# 05I2S.net
KiCad netlist of a schematic drawn in Altium Designer
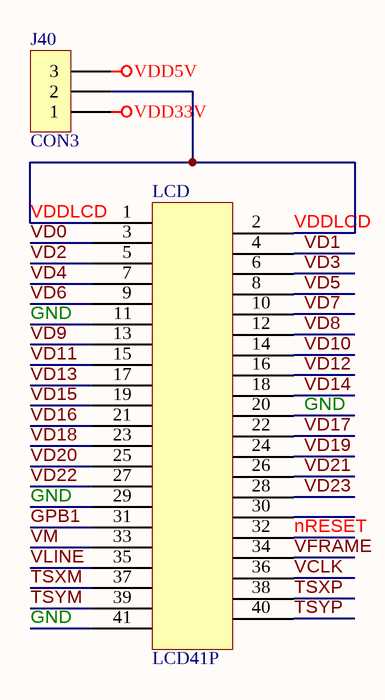
[diagram p0: 05I2S.SchDoc]

(export (version "E")
  (design (tool "Eeschema 10.0.6"))
  (components
    (comp (ref "J40")
      (value "CON3")
      (footprint "HDR1X3")
      (description "Connector")
      (libsource (lib "*") (part "CON3"))
    )
    (comp (ref "LCD") (value "LCD41P") (footprint "FPC40") (libsource (lib "*") (part "LCD41P")))
  )
  (nets
    (net (code "1") (name "/GND") (class "Default")
      (node (ref "LCD") (pin "11") (pintype "passive"))
      (node (ref "LCD") (pin "20") (pintype "passive"))
      (node (ref "LCD") (pin "29") (pintype "passive"))
      (node (ref "LCD") (pin "41") (pintype "passive"))
    )
    (net (code "2") (name "/GPB1") (class "Default") (node (ref "LCD") (pin "31") (pintype "passive")))
    (net (code "3") (name "/TSXM") (class "Default") (node (ref "LCD") (pin "37") (pintype "passive")))
    (net (code "4") (name "/TSXP") (class "Default") (node (ref "LCD") (pin "38") (pintype "passive")))
    (net (code "5") (name "/TSYM") (class "Default") (node (ref "LCD") (pin "39") (pintype "passive")))
    (net (code "6") (name "/TSYP") (class "Default") (node (ref "LCD") (pin "40") (pintype "passive")))
    (net (code "7") (name "/VCLK") (class "Default") (node (ref "LCD") (pin "36") (pintype "passive")))
    (net (code "8") (name "/VD0") (class "Default") (node (ref "LCD") (pin "3") (pintype "passive")))
    (net (code "9") (name "/VD1") (class "Default") (node (ref "LCD") (pin "4") (pintype "passive")))
    (net (code "10") (name "/VD2") (class "Default") (node (ref "LCD") (pin "5") (pintype "passive")))
    (net (code "11") (name "/VD3") (class "Default") (node (ref "LCD") (pin "6") (pintype "passive")))
    (net (code "12") (name "/VD4") (class "Default") (node (ref "LCD") (pin "7") (pintype "passive")))
    (net (code "13") (name "/VD5") (class "Default") (node (ref "LCD") (pin "8") (pintype "passive")))
    (net (code "14") (name "/VD6") (class "Default") (node (ref "LCD") (pin "9") (pintype "passive")))
    (net (code "15") (name "/VD7") (class "Default") (node (ref "LCD") (pin "10") (pintype "passive")))
    (net (code "16") (name "/VD8") (class "Default") (node (ref "LCD") (pin "12") (pintype "passive")))
    (net (code "17") (name "/VD9") (class "Default") (node (ref "LCD") (pin "13") (pintype "passive")))
    (net (code "18") (name "/VD10") (class "Default") (node (ref "LCD") (pin "14") (pintype "passive")))
    (net (code "19") (name "/VD11") (class "Default") (node (ref "LCD") (pin "15") (pintype "passive")))
    (net (code "20") (name "/VD12") (class "Default") (node (ref "LCD") (pin "16") (pintype "passive")))
    (net (code "21") (name "/VD13") (class "Default") (node (ref "LCD") (pin "17") (pintype "passive")))
    (net (code "22") (name "/VD14") (class "Default") (node (ref "LCD") (pin "18") (pintype "passive")))
    (net (code "23") (name "/VD15") (class "Default") (node (ref "LCD") (pin "19") (pintype "passive")))
    (net (code "24") (name "/VD16") (class "Default") (node (ref "LCD") (pin "21") (pintype "passive")))
    (net (code "25") (name "/VD17") (class "Default") (node (ref "LCD") (pin "22") (pintype "passive")))
    (net (code "26") (name "/VD18") (class "Default") (node (ref "LCD") (pin "23") (pintype "passive")))
    (net (code "27") (name "/VD19") (class "Default") (node (ref "LCD") (pin "24") (pintype "passive")))
    (net (code "28") (name "/VD20") (class "Default") (node (ref "LCD") (pin "25") (pintype "passive")))
    (net (code "29") (name "/VD21") (class "Default") (node (ref "LCD") (pin "26") (pintype "passive")))
    (net (code "30") (name "/VD22") (class "Default") (node (ref "LCD") (pin "27") (pintype "passive")))
    (net (code "31") (name "/VD23") (class "Default") (node (ref "LCD") (pin "28") (pintype "passive")))
    (net (code "32") (name "/VDDLCD") (class "Default")
      (node (ref "J40") (pin "2") (pinfunction "2_2") (pintype "passive"))
      (node (ref "LCD") (pin "1") (pintype "passive"))
      (node (ref "LCD") (pin "2") (pintype "passive"))
    )
    (net (code "33") (name "/VFRAME") (class "Default") (node (ref "LCD") (pin "34") (pintype "passive")))
    (net (code "34") (name "/VLINE") (class "Default") (node (ref "LCD") (pin "35") (pintype "passive")))
    (net (code "35") (name "/VM") (class "Default") (node (ref "LCD") (pin "33") (pintype "passive")))
    (net (code "36") (name "/nRESET") (class "Default") (node (ref "LCD") (pin "32") (pintype "passive")))
    (net (code "37") (name "VDD5V") (class "Default")
      (node (ref "J40") (pin "3") (pinfunction "3_3") (pintype "passive"))
    )
    (net (code "38") (name "VDD33V") (class "Default")
      (node (ref "J40") (pin "1") (pinfunction "1_1") (pintype "passive"))
    )
    (net (code "39") (name "unconnected-(LCD-Pad30)") (class "Default")
      (node (ref "LCD") (pin "30") (pintype "passive"))
    )
  )
)
